# bat_connectors.net
KiCad netlist of a schematic drawn in Altium Designer
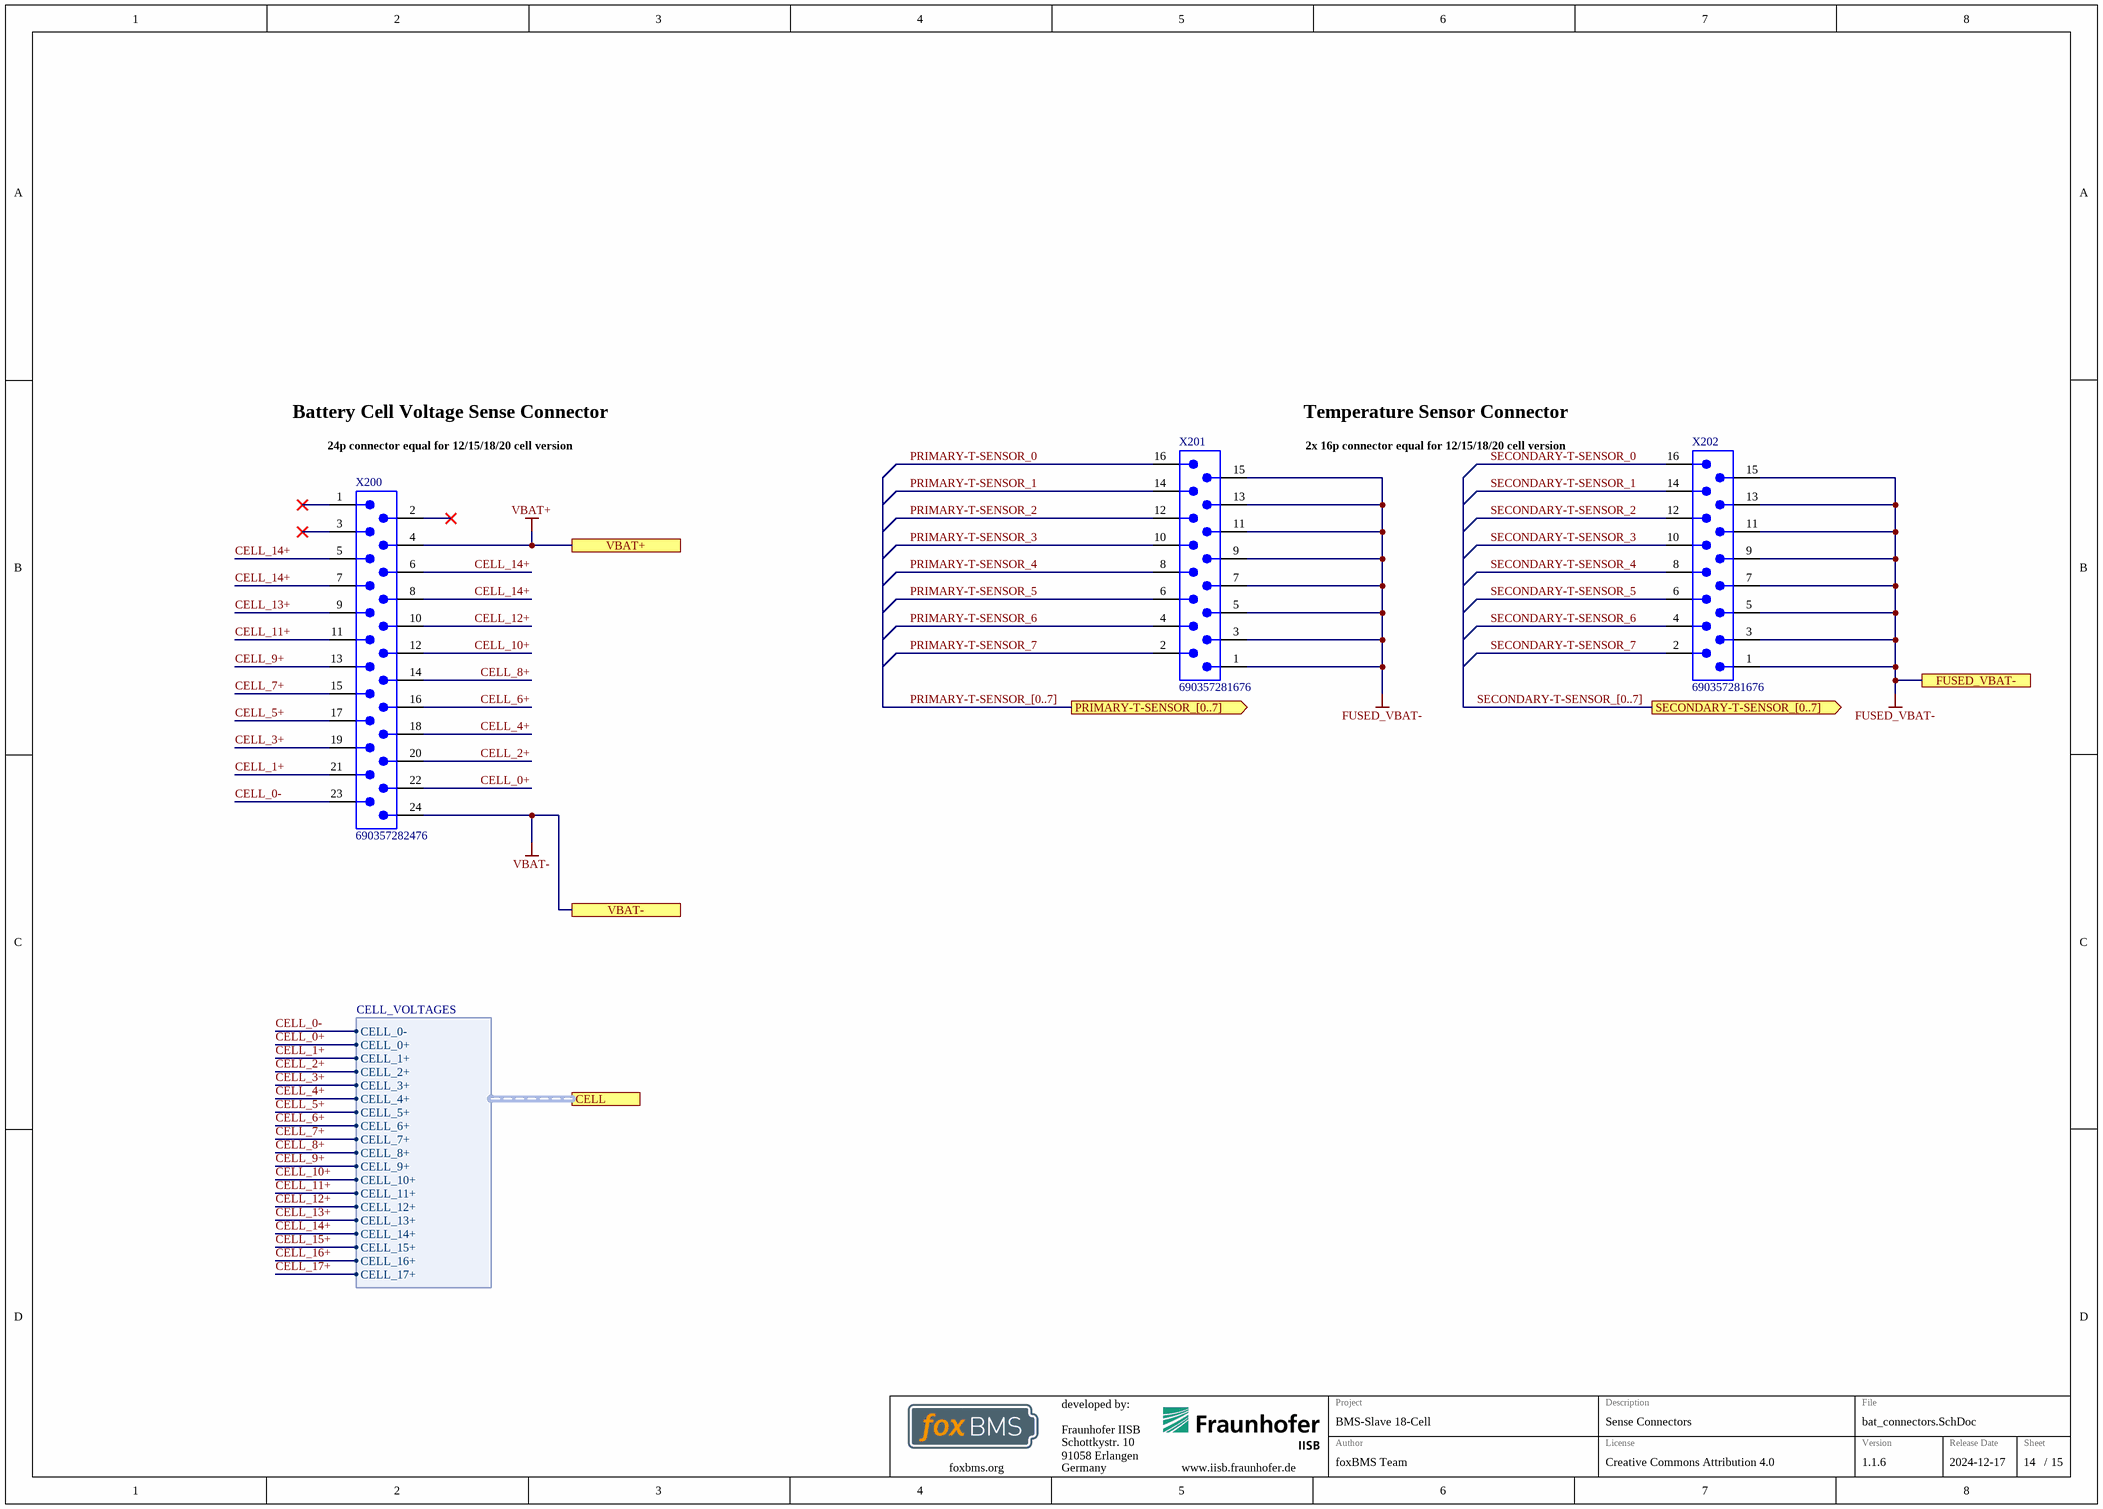
[diagram p0: bat_connectors.SchDoc]

(export (version "E")
  (design (tool "Eeschema 10.0.6"))
  (components
    (comp (ref "X200")
      (value "690357282476")
      (footprint "690357282476")
      (libsource (lib "Altium Content Vault") (part "MM_Male_24P"))
    )
    (comp (ref "X201")
      (value "690357281676")
      (footprint "690357281676")
      (libsource (lib "Altium Content Vault") (part "MM_Male_16P"))
    )
    (comp (ref "X202")
      (value "690357281676")
      (footprint "690357281676")
      (libsource (lib "Altium Content Vault") (part "MM_Male_16P"))
    )
  )
  (nets
    (net (code "2") (name "/CELL_0+") (class "Default")
      (node (ref "X200") (pin "22") (pinfunction "22_22") (pintype "passive"))
    )
    (net (code "3") (name "/CELL_0-") (class "Default")
      (node (ref "X200") (pin "23") (pinfunction "23_23") (pintype "passive"))
    )
    (net (code "4") (name "/CELL_1+") (class "Default")
      (node (ref "X200") (pin "21") (pinfunction "21_21") (pintype "passive"))
    )
    (net (code "5") (name "/CELL_2+") (class "Default")
      (node (ref "X200") (pin "20") (pinfunction "20_20") (pintype "passive"))
    )
    (net (code "6") (name "/CELL_3+") (class "Default")
      (node (ref "X200") (pin "19") (pinfunction "19_19") (pintype "passive"))
    )
    (net (code "7") (name "/CELL_4+") (class "Default")
      (node (ref "X200") (pin "18") (pinfunction "18_18") (pintype "passive"))
    )
    (net (code "8") (name "/CELL_5+") (class "Default")
      (node (ref "X200") (pin "17") (pinfunction "17_17") (pintype "passive"))
    )
    (net (code "9") (name "/CELL_6+") (class "Default")
      (node (ref "X200") (pin "16") (pinfunction "16_16") (pintype "passive"))
    )
    (net (code "10") (name "/CELL_7+") (class "Default")
      (node (ref "X200") (pin "15") (pinfunction "15_15") (pintype "passive"))
    )
    (net (code "11") (name "/CELL_8+") (class "Default")
      (node (ref "X200") (pin "14") (pinfunction "14_14") (pintype "passive"))
    )
    (net (code "12") (name "/CELL_9+") (class "Default")
      (node (ref "X200") (pin "13") (pinfunction "13_13") (pintype "passive"))
    )
    (net (code "13") (name "/CELL_10+") (class "Default")
      (node (ref "X200") (pin "12") (pinfunction "12_12") (pintype "passive"))
    )
    (net (code "14") (name "/CELL_11+") (class "Default")
      (node (ref "X200") (pin "11") (pinfunction "11_11") (pintype "passive"))
    )
    (net (code "15") (name "/CELL_12+") (class "Default")
      (node (ref "X200") (pin "10") (pinfunction "10_10") (pintype "passive"))
    )
    (net (code "16") (name "/CELL_13+") (class "Default")
      (node (ref "X200") (pin "9") (pinfunction "9_9") (pintype "passive"))
    )
    (net (code "17") (name "/CELL_14+") (class "Default")
      (node (ref "X200") (pin "5") (pinfunction "5_5") (pintype "passive"))
      (node (ref "X200") (pin "6") (pinfunction "6_6") (pintype "passive"))
      (node (ref "X200") (pin "7") (pinfunction "7_7") (pintype "passive"))
      (node (ref "X200") (pin "8") (pinfunction "8_8") (pintype "passive"))
    )
    (net (code "21") (name "/PRIMARY-T-SENSOR_0") (class "Default")
      (node (ref "X201") (pin "16") (pinfunction "16_16") (pintype "passive"))
    )
    (net (code "22") (name "/PRIMARY-T-SENSOR_1") (class "Default")
      (node (ref "X201") (pin "14") (pinfunction "14_14") (pintype "passive"))
    )
    (net (code "23") (name "/PRIMARY-T-SENSOR_2") (class "Default")
      (node (ref "X201") (pin "12") (pinfunction "12_12") (pintype "passive"))
    )
    (net (code "24") (name "/PRIMARY-T-SENSOR_3") (class "Default")
      (node (ref "X201") (pin "10") (pinfunction "10_10") (pintype "passive"))
    )
    (net (code "25") (name "/PRIMARY-T-SENSOR_4") (class "Default")
      (node (ref "X201") (pin "8") (pinfunction "8_8") (pintype "passive"))
    )
    (net (code "26") (name "/PRIMARY-T-SENSOR_5") (class "Default")
      (node (ref "X201") (pin "6") (pinfunction "6_6") (pintype "passive"))
    )
    (net (code "27") (name "/PRIMARY-T-SENSOR_6") (class "Default")
      (node (ref "X201") (pin "4") (pinfunction "4_4") (pintype "passive"))
    )
    (net (code "28") (name "/PRIMARY-T-SENSOR_7") (class "Default")
      (node (ref "X201") (pin "2") (pinfunction "2_2") (pintype "passive"))
    )
    (net (code "30") (name "/SECONDARY-T-SENSOR_0") (class "Default")
      (node (ref "X202") (pin "16") (pinfunction "16_16") (pintype "passive"))
    )
    (net (code "31") (name "/SECONDARY-T-SENSOR_1") (class "Default")
      (node (ref "X202") (pin "14") (pinfunction "14_14") (pintype "passive"))
    )
    (net (code "32") (name "/SECONDARY-T-SENSOR_2") (class "Default")
      (node (ref "X202") (pin "12") (pinfunction "12_12") (pintype "passive"))
    )
    (net (code "33") (name "/SECONDARY-T-SENSOR_3") (class "Default")
      (node (ref "X202") (pin "10") (pinfunction "10_10") (pintype "passive"))
    )
    (net (code "34") (name "/SECONDARY-T-SENSOR_4") (class "Default")
      (node (ref "X202") (pin "8") (pinfunction "8_8") (pintype "passive"))
    )
    (net (code "35") (name "/SECONDARY-T-SENSOR_5") (class "Default")
      (node (ref "X202") (pin "6") (pinfunction "6_6") (pintype "passive"))
    )
    (net (code "36") (name "/SECONDARY-T-SENSOR_6") (class "Default")
      (node (ref "X202") (pin "4") (pinfunction "4_4") (pintype "passive"))
    )
    (net (code "37") (name "/SECONDARY-T-SENSOR_7") (class "Default")
      (node (ref "X202") (pin "2") (pinfunction "2_2") (pintype "passive"))
    )
    (net (code "40") (name "FUSED_VBAT-") (class "Default")
      (node (ref "X201") (pin "1") (pinfunction "1_1") (pintype "passive"))
      (node (ref "X201") (pin "11") (pinfunction "11_11") (pintype "passive"))
      (node (ref "X201") (pin "13") (pinfunction "13_13") (pintype "passive"))
      (node (ref "X201") (pin "15") (pinfunction "15_15") (pintype "passive"))
      (node (ref "X201") (pin "3") (pinfunction "3_3") (pintype "passive"))
      (node (ref "X201") (pin "5") (pinfunction "5_5") (pintype "passive"))
      (node (ref "X201") (pin "7") (pinfunction "7_7") (pintype "passive"))
      (node (ref "X201") (pin "9") (pinfunction "9_9") (pintype "passive"))
      (node (ref "X202") (pin "1") (pinfunction "1_1") (pintype "passive"))
      (node (ref "X202") (pin "11") (pinfunction "11_11") (pintype "passive"))
      (node (ref "X202") (pin "13") (pinfunction "13_13") (pintype "passive"))
      (node (ref "X202") (pin "15") (pinfunction "15_15") (pintype "passive"))
      (node (ref "X202") (pin "3") (pinfunction "3_3") (pintype "passive"))
      (node (ref "X202") (pin "5") (pinfunction "5_5") (pintype "passive"))
      (node (ref "X202") (pin "7") (pinfunction "7_7") (pintype "passive"))
      (node (ref "X202") (pin "9") (pinfunction "9_9") (pintype "passive"))
    )
    (net (code "41") (name "VBAT+") (class "Default")
      (node (ref "X200") (pin "4") (pinfunction "4_4") (pintype "passive"))
    )
    (net (code "42") (name "VBAT-") (class "Default")
      (node (ref "X200") (pin "24") (pinfunction "24_24") (pintype "passive"))
    )
    (net (code "43") (name "unconnected-(X200-Pad1)") (class "Default")
      (node (ref "X200") (pin "1") (pinfunction "1_1") (pintype "passive+no_connect"))
    )
    (net (code "44") (name "unconnected-(X200-Pad2)") (class "Default")
      (node (ref "X200") (pin "2") (pinfunction "2_2") (pintype "passive+no_connect"))
    )
    (net (code "45") (name "unconnected-(X200-Pad3)") (class "Default")
      (node (ref "X200") (pin "3") (pinfunction "3_3") (pintype "passive+no_connect"))
    )
  )
)
